# SparkFun_Soft_Power_Switch.net
KiCad netlist of a schematic drawn in EAGLE
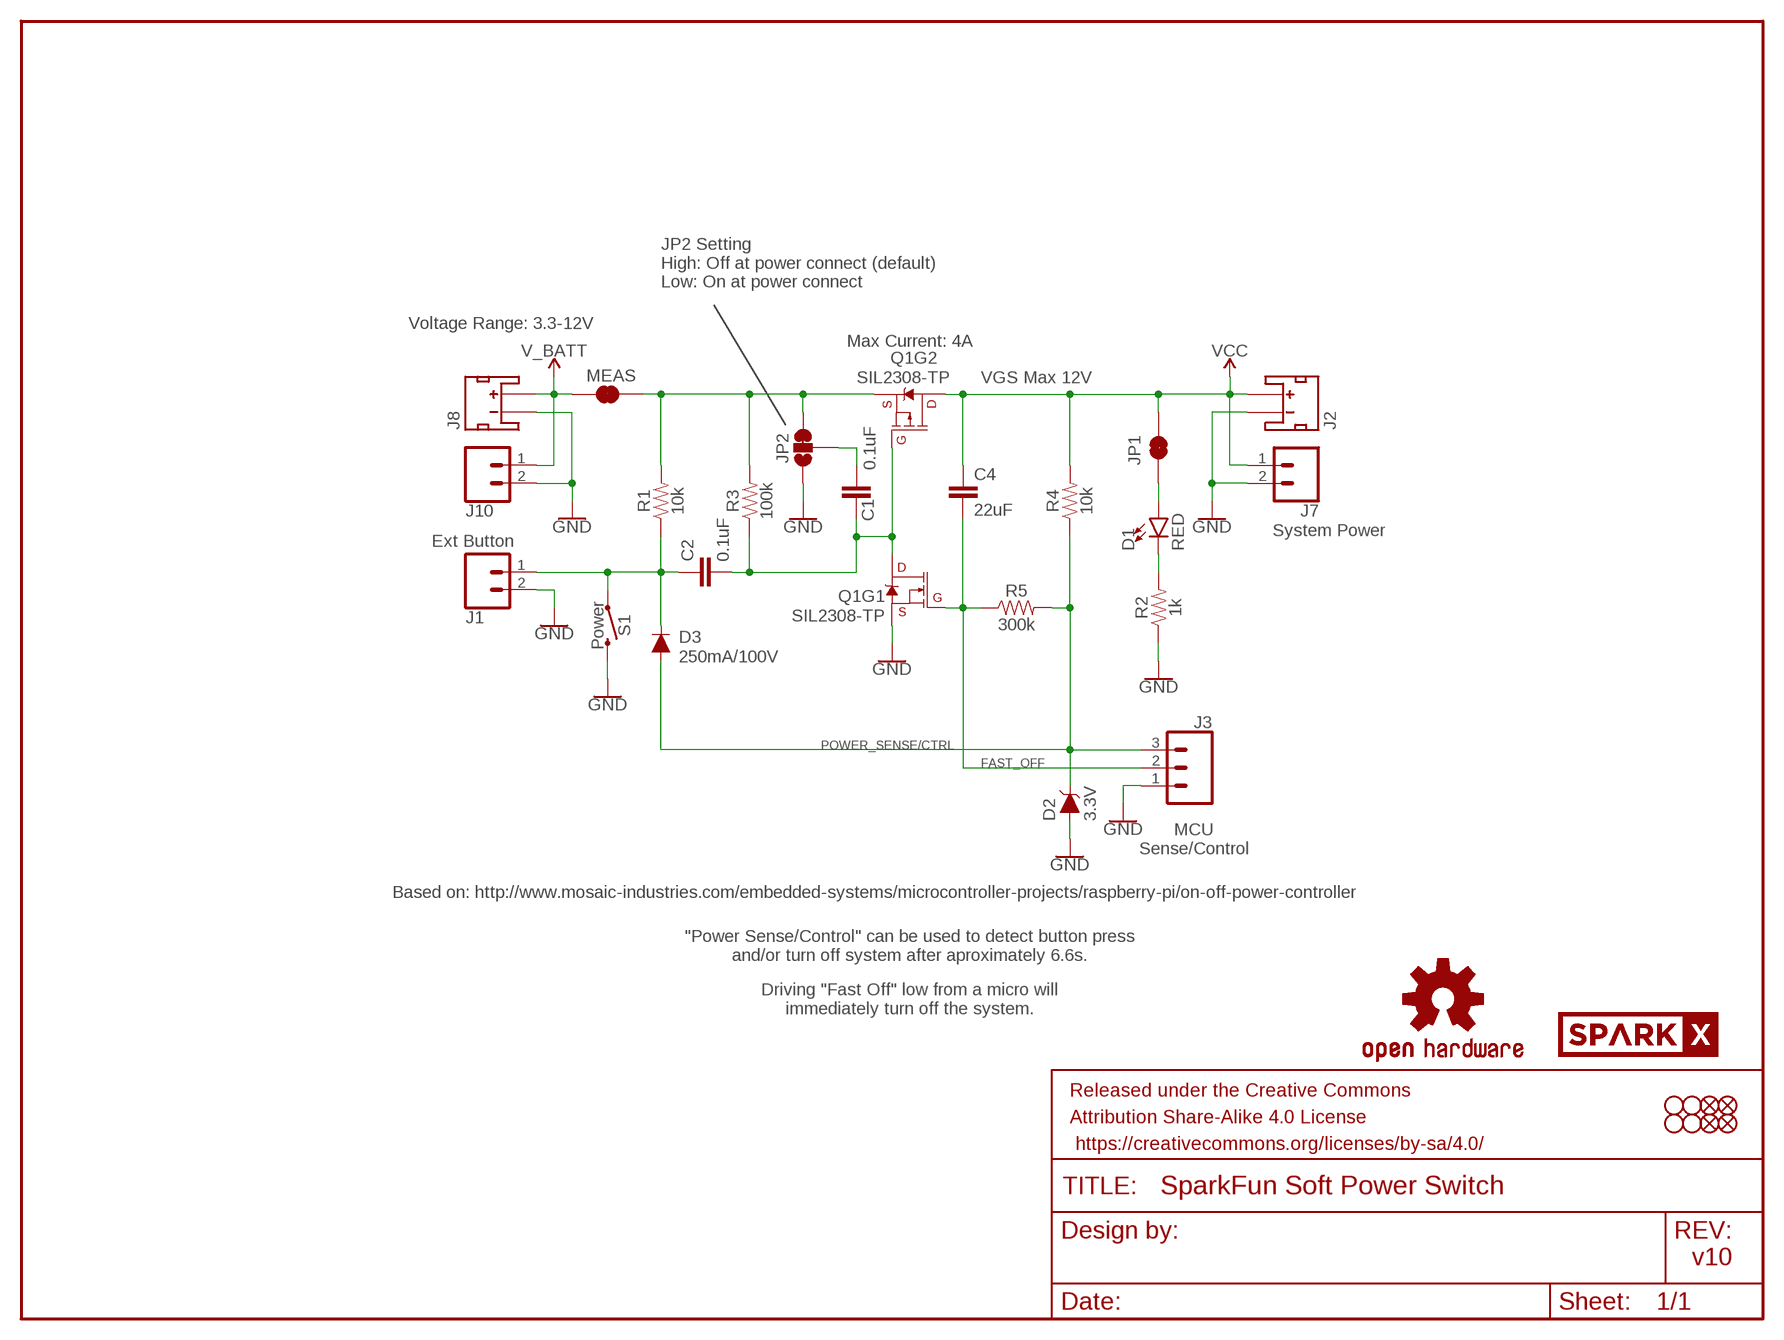
[diagram p0: schematic, sheet 1]

(export (version "E")
  (design (tool "Eeschema 10.0.6"))
  (components
    (comp (ref "C1")
      (value "0.1uF")
      (footprint "eagle-import:0603")
      (libsource (lib "eagle-import") (part "0.1UF-0603-25V-5%"))
    )
    (comp (ref "C2")
      (value "0.1uF")
      (footprint "eagle-import:0603")
      (libsource (lib "eagle-import") (part "0.1UF-0603-25V-5%"))
    )
    (comp (ref "C4")
      (value "22uF")
      (footprint "eagle-import:0805")
      (libsource (lib "eagle-import") (part "22UF-0805-16V-20%"))
    )
    (comp (ref "D1")
      (value "RED")
      (footprint "eagle-import:LED-0603")
      (libsource (lib "eagle-import") (part "LED-RED0603"))
    )
    (comp (ref "D2")
      (value "3.3V")
      (footprint "eagle-import:SOD-323")
      (libsource (lib "eagle-import") (part "DIODE-ZENER-MM3Z3V3T1G"))
    )
    (comp (ref "D3")
      (value "250mA/100V")
      (footprint "eagle-import:SOD-323")
      (libsource (lib "eagle-import") (part "DIODE-BAS16J"))
    )
    (comp (ref "FD1")
      (value "FIDUCIAL1X2")
      (footprint "eagle-import:FIDUCIAL-1X2")
      (libsource (lib "eagle-import") (part "FIDUCIAL1X2"))
    )
    (comp (ref "FD2")
      (value "FIDUCIAL1X2")
      (footprint "eagle-import:FIDUCIAL-1X2")
      (libsource (lib "eagle-import") (part "FIDUCIAL1X2"))
    )
    (comp (ref "FD3")
      (value "FIDUCIAL1X2")
      (footprint "eagle-import:FIDUCIAL-1X2")
      (libsource (lib "eagle-import") (part "FIDUCIAL1X2"))
    )
    (comp (ref "FD4")
      (value "FIDUCIAL1X2")
      (footprint "eagle-import:FIDUCIAL-1X2")
      (libsource (lib "eagle-import") (part "FIDUCIAL1X2"))
    )
    (comp (ref "FRAME1")
      (value "FRAME-LETTER")
      (footprint "eagle-import:CREATIVE_COMMONS")
      (libsource (lib "eagle-import") (part "FRAME-LETTER"))
    )
    (comp (ref "H1")
      (value "STAND-OFF")
      (footprint "eagle-import:STAND-OFF")
      (libsource (lib "eagle-import") (part "STAND-OFF"))
    )
    (comp (ref "H2")
      (value "STAND-OFF")
      (footprint "eagle-import:STAND-OFF")
      (libsource (lib "eagle-import") (part "STAND-OFF"))
    )
    (comp (ref "H3")
      (value "STAND-OFF")
      (footprint "eagle-import:STAND-OFF")
      (libsource (lib "eagle-import") (part "STAND-OFF"))
    )
    (comp (ref "H4")
      (value "STAND-OFF")
      (footprint "eagle-import:STAND-OFF")
      (libsource (lib "eagle-import") (part "STAND-OFF"))
    )
    (comp (ref "J1")
      (value "Ext Button")
      (footprint "eagle-import:1X02_NO_SILK")
      (libsource (lib "eagle-import") (part "CONN_021X02_NO_SILK"))
    )
    (comp (ref "J2")
      (value "JST_2MM_MALE")
      (footprint "eagle-import:JST-2-SMD")
      (libsource (lib "eagle-import") (part "JST_2MM_MALE"))
    )
    (comp (ref "J3")
      (value "CONN_031X03_NO_SILK")
      (footprint "eagle-import:1X03_NO_SILK")
      (libsource (lib "eagle-import") (part "CONN_031X03_NO_SILK"))
    )
    (comp (ref "J7")
      (value "System Power")
      (footprint "eagle-import:1X02_NO_SILK")
      (libsource (lib "eagle-import") (part "CONN_021X02_NO_SILK"))
    )
    (comp (ref "J8")
      (value "JST_2MM_MALE")
      (footprint "eagle-import:JST-2-SMD")
      (libsource (lib "eagle-import") (part "JST_2MM_MALE"))
    )
    (comp (ref "J10")
      (value "CONN_021X02_NO_SILK")
      (footprint "eagle-import:1X02_NO_SILK")
      (libsource (lib "eagle-import") (part "CONN_021X02_NO_SILK"))
    )
    (comp (ref "JP1")
      (value "JUMPER-SMT_2_NC_TRACE_SILK")
      (footprint "eagle-import:SMT-JUMPER_2_NC_TRACE_SILK")
      (libsource (lib "eagle-import") (part "JUMPER-SMT_2_NC_TRACE_SILK"))
    )
    (comp (ref "JP2")
      (value "JUMPER-SMT_3_1-NC_TRACE_SILK")
      (footprint "eagle-import:SMT-JUMPER_3_1-NC_TRACE_SILK")
      (libsource (lib "eagle-import") (part "JUMPER-SMT_3_1-NC_TRACE_SILK"))
    )
    (comp (ref "LOGO1")
      (value "OSHW-LOGOS")
      (footprint "eagle-import:OSHW-LOGO-S")
      (libsource (lib "eagle-import") (part "OSHW-LOGOS"))
    )
    (comp (ref "MEAS")
      (value "JUMPER-COMBO_2_NC_TRACE")
      (footprint "eagle-import:COMBO-JUMPER_2_NC_TRACE")
      (libsource (lib "eagle-import") (part "JUMPER-COMBO_2_NC_TRACE"))
    )
    (comp (ref "Q1")
      (value "SIL2308-TP")
      (footprint "eagle-import:SOT26")
      (libsource (lib "eagle-import") (part "MOSFET_COMPLIMENTARY_PAIR-SIL2308"))
    )
    (comp (ref "R1")
      (value "10k")
      (footprint "eagle-import:0603")
      (libsource (lib "eagle-import") (part "10KOHM-0603-1/10W-1%"))
    )
    (comp (ref "R2")
      (value "1k")
      (footprint "eagle-import:0603")
      (libsource (lib "eagle-import") (part "1KOHM-0603-1/10W-1%"))
    )
    (comp (ref "R3")
      (value "100k")
      (footprint "eagle-import:0603")
      (libsource (lib "eagle-import") (part "100KOHM-0603-1/10W-1%"))
    )
    (comp (ref "R4")
      (value "10k")
      (footprint "eagle-import:0603")
      (libsource (lib "eagle-import") (part "10KOHM-0603-1/10W-1%"))
    )
    (comp (ref "R5")
      (value "300k")
      (footprint "eagle-import:0603")
      (libsource (lib "eagle-import") (part "300KOHM-0603-1/10W-1%"))
    )
    (comp (ref "S1")
      (value "Power")
      (footprint "eagle-import:TACTILE_SWITCH_SMD_5.2MM")
      (libsource (lib "eagle-import") (part "MOMENTARY-SWITCH-SPST-SMD-5.2MM-TALL"))
    )
    (comp (ref "U$1")
      (value "SPARKX-LOGO3")
      (footprint "eagle-import:SPARKX-SMALL")
      (libsource (lib "eagle-import") (part "SPARKX-LOGO3"))
    )
    (comp (ref "U$15")
      (value "SPARKX-LOGO2")
      (footprint "eagle-import:SPARKX-TINY")
      (libsource (lib "eagle-import") (part "SPARKX-LOGO2"))
    )
  )
  (nets
    (net (code "1") (name "/FAST_OFF") (class "Default")
      (node (ref "C4") (pin "2") (pinfunction "2_2") (pintype "passive"))
      (node (ref "J3") (pin "2") (pinfunction "2_2") (pintype "passive"))
      (node (ref "Q1") (pin "G1") (pinfunction "G_G1") (pintype "bidirectional"))
      (node (ref "R5") (pin "1") (pinfunction "1_1") (pintype "passive"))
    )
    (net (code "2") (name "/POWER_SENSE{slash}CTRL") (class "Default")
      (node (ref "D2") (pin "C") (pinfunction "C_C") (pintype "passive"))
      (node (ref "D3") (pin "A") (pinfunction "A_A") (pintype "passive"))
      (node (ref "J3") (pin "3") (pinfunction "3_3") (pintype "passive"))
      (node (ref "R4") (pin "1") (pinfunction "1_1") (pintype "passive"))
      (node (ref "R5") (pin "2") (pinfunction "2_2") (pintype "passive"))
    )
    (net (code "3") (name "GND") (class "Default")
      (node (ref "D2") (pin "A") (pinfunction "A_A") (pintype "passive"))
      (node (ref "J1") (pin "2") (pinfunction "2_2") (pintype "passive"))
      (node (ref "J10") (pin "2") (pinfunction "2_2") (pintype "passive"))
      (node (ref "J2") (pin "1") (pinfunction "-_1") (pintype "bidirectional"))
      (node (ref "J3") (pin "1") (pinfunction "1_1") (pintype "passive"))
      (node (ref "J7") (pin "2") (pinfunction "2_2") (pintype "passive"))
      (node (ref "J8") (pin "1") (pinfunction "-_1") (pintype "bidirectional"))
      (node (ref "JP2") (pin "1") (pinfunction "1_1") (pintype "passive"))
      (node (ref "Q1") (pin "S1") (pinfunction "S_S1") (pintype "bidirectional"))
      (node (ref "R2") (pin "1") (pinfunction "1_1") (pintype "passive"))
      (node (ref "S1") (pin "3") (pinfunction "2_3") (pintype "passive"))
    )
    (net (code "4") (name "Net-(C1-Pad2)") (class "Default")
      (node (ref "C1") (pin "2") (pinfunction "2_2") (pintype "passive"))
      (node (ref "JP2") (pin "2") (pinfunction "2_2") (pintype "passive"))
    )
    (net (code "5") (name "Net-(C2-Pad1)") (class "Default")
      (node (ref "C2") (pin "1") (pinfunction "1_1") (pintype "passive"))
      (node (ref "D3") (pin "C") (pinfunction "C_C") (pintype "passive"))
      (node (ref "J1") (pin "1") (pinfunction "1_1") (pintype "passive"))
      (node (ref "R1") (pin "1") (pinfunction "1_1") (pintype "passive"))
      (node (ref "S1") (pin "1") (pinfunction "1_1") (pintype "passive"))
    )
    (net (code "6") (name "Net-(D1-PadA)") (class "Default")
      (node (ref "D1") (pin "A") (pinfunction "A_A") (pintype "passive"))
      (node (ref "JP1") (pin "1") (pinfunction "1_1") (pintype "passive"))
    )
    (net (code "7") (name "Net-(D1-PadC)") (class "Default")
      (node (ref "D1") (pin "C") (pinfunction "C_C") (pintype "passive"))
      (node (ref "R2") (pin "2") (pinfunction "2_2") (pintype "passive"))
    )
    (net (code "8") (name "Net-(Q1A-D)") (class "Default")
      (node (ref "C1") (pin "1") (pinfunction "1_1") (pintype "passive"))
      (node (ref "C2") (pin "2") (pinfunction "2_2") (pintype "passive"))
      (node (ref "Q1") (pin "D1") (pinfunction "D_D1") (pintype "bidirectional"))
      (node (ref "Q1") (pin "G2") (pinfunction "G_G2") (pintype "bidirectional"))
      (node (ref "R3") (pin "1") (pinfunction "1_1") (pintype "passive"))
    )
    (net (code "9") (name "Net-(Q1B-S)") (class "Default")
      (node (ref "JP2") (pin "3") (pinfunction "3_3") (pintype "passive"))
      (node (ref "MEAS") (pin "2") (pinfunction "2_2") (pintype "passive"))
      (node (ref "MEAS") (pin "4") (pinfunction "2_4") (pintype "passive"))
      (node (ref "Q1") (pin "S2") (pinfunction "S_S2") (pintype "bidirectional"))
      (node (ref "R1") (pin "2") (pinfunction "2_2") (pintype "passive"))
      (node (ref "R3") (pin "2") (pinfunction "2_2") (pintype "passive"))
    )
    (net (code "10") (name "VCC") (class "Default")
      (node (ref "C4") (pin "1") (pinfunction "1_1") (pintype "passive"))
      (node (ref "J2") (pin "2") (pinfunction "+_2") (pintype "bidirectional"))
      (node (ref "J7") (pin "1") (pinfunction "1_1") (pintype "passive"))
      (node (ref "JP1") (pin "2") (pinfunction "2_2") (pintype "passive"))
      (node (ref "Q1") (pin "D2") (pinfunction "D_D2") (pintype "bidirectional"))
      (node (ref "R4") (pin "2") (pinfunction "2_2") (pintype "passive"))
    )
    (net (code "11") (name "V_BATT") (class "Default")
      (node (ref "J10") (pin "1") (pinfunction "1_1") (pintype "passive"))
      (node (ref "J8") (pin "2") (pinfunction "+_2") (pintype "bidirectional"))
      (node (ref "MEAS") (pin "1") (pinfunction "1_1") (pintype "passive"))
      (node (ref "MEAS") (pin "3") (pinfunction "1_3") (pintype "passive"))
    )
    (net (code "12") (name "unconnected-(J2-PAD1-PadNC1)") (class "Default")
      (node (ref "J2") (pin "NC1") (pinfunction "PAD1_NC1") (pintype "bidirectional"))
    )
    (net (code "13") (name "unconnected-(J2-PAD2-PadNC2)") (class "Default")
      (node (ref "J2") (pin "NC2") (pinfunction "PAD2_NC2") (pintype "bidirectional"))
    )
    (net (code "14") (name "unconnected-(J8-PAD1-PadNC1)") (class "Default")
      (node (ref "J8") (pin "NC1") (pinfunction "PAD1_NC1") (pintype "bidirectional"))
    )
    (net (code "15") (name "unconnected-(J8-PAD2-PadNC2)") (class "Default")
      (node (ref "J8") (pin "NC2") (pinfunction "PAD2_NC2") (pintype "bidirectional"))
    )
  )
)
